# 2_FPGA.net
KiCad netlist of a schematic drawn in Altium Designer
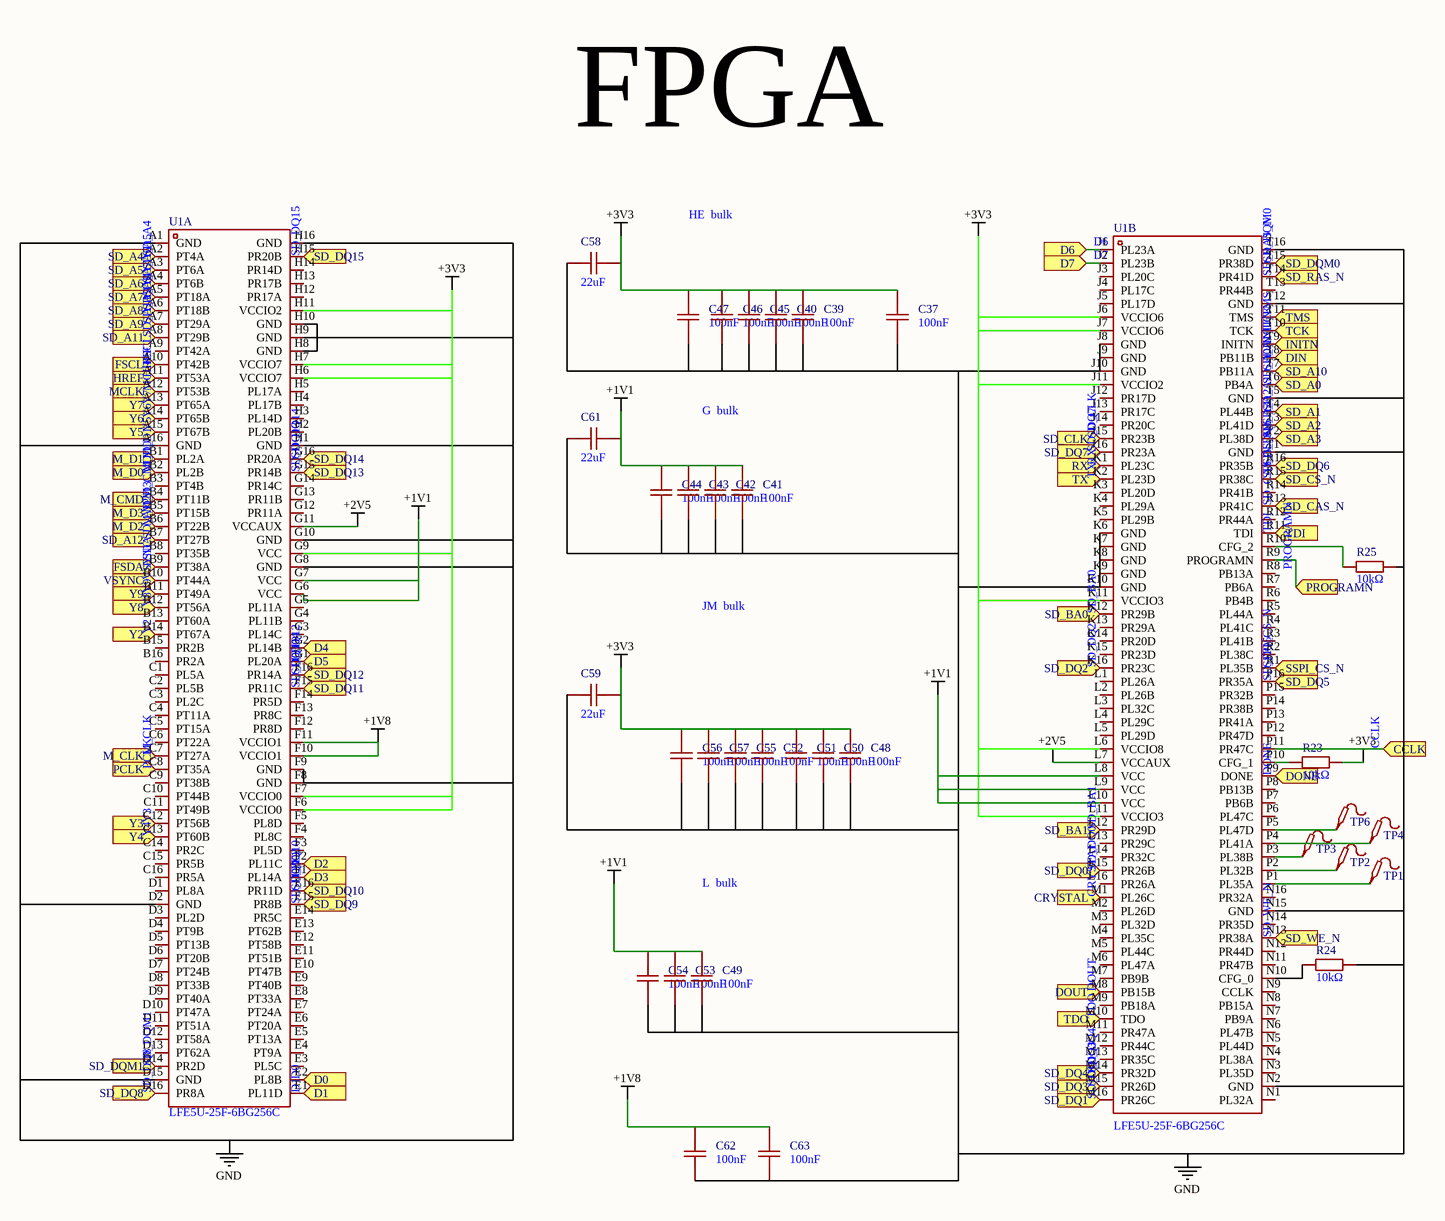
[diagram p0: 2_FPGA.schdoc]

(export (version "E")
  (design (tool "Eeschema 10.0.6"))
  (components
    (comp (ref "C37")
      (value "100nF")
      (footprint "C01005")
      (fields
        (field (name "MANUFACTURER") "muRata(村田)")
        (field (name "MANUFACTURER PART") "GRM022R60J104KE15D")
        (field (name "TOLERANCE") "±10%")
      )
      (libsource (lib "altium-import") (part "root_2_GRM022R60J104KE15D_"))
    )
    (comp (ref "C39")
      (value "100nF")
      (footprint "C01005")
      (fields
        (field (name "MANUFACTURER") "muRata(村田)")
        (field (name "MANUFACTURER PART") "GRM022R60J104KE15D")
        (field (name "TOLERANCE") "±10%")
      )
      (libsource (lib "altium-import") (part "root_2_GRM022R60J104KE15D_"))
    )
    (comp (ref "C40")
      (value "100nF")
      (footprint "C01005")
      (fields
        (field (name "MANUFACTURER") "muRata(村田)")
        (field (name "MANUFACTURER PART") "GRM022R60J104KE15D")
        (field (name "TOLERANCE") "±10%")
      )
      (libsource (lib "altium-import") (part "root_2_GRM022R60J104KE15D_"))
    )
    (comp (ref "C41")
      (value "100nF")
      (footprint "C01005")
      (fields
        (field (name "MANUFACTURER") "muRata(村田)")
        (field (name "MANUFACTURER PART") "GRM022R60J104KE15D")
        (field (name "TOLERANCE") "±10%")
      )
      (libsource (lib "altium-import") (part "root_2_GRM022R60J104KE15D_"))
    )
    (comp (ref "C42")
      (value "100nF")
      (footprint "C01005")
      (fields
        (field (name "MANUFACTURER") "muRata(村田)")
        (field (name "MANUFACTURER PART") "GRM022R60J104KE15D")
        (field (name "TOLERANCE") "±10%")
      )
      (libsource (lib "altium-import") (part "root_2_GRM022R60J104KE15D_"))
    )
    (comp (ref "C43")
      (value "100nF")
      (footprint "C01005")
      (fields
        (field (name "MANUFACTURER") "muRata(村田)")
        (field (name "MANUFACTURER PART") "GRM022R60J104KE15D")
        (field (name "TOLERANCE") "±10%")
      )
      (libsource (lib "altium-import") (part "root_2_GRM022R60J104KE15D_"))
    )
    (comp (ref "C44")
      (value "100nF")
      (footprint "C01005")
      (fields
        (field (name "MANUFACTURER") "muRata(村田)")
        (field (name "MANUFACTURER PART") "GRM022R60J104KE15D")
        (field (name "TOLERANCE") "±10%")
      )
      (libsource (lib "altium-import") (part "root_2_GRM022R60J104KE15D_"))
    )
    (comp (ref "C45")
      (value "100nF")
      (footprint "C01005")
      (fields
        (field (name "MANUFACTURER") "muRata(村田)")
        (field (name "MANUFACTURER PART") "GRM022R60J104KE15D")
        (field (name "TOLERANCE") "±10%")
      )
      (libsource (lib "altium-import") (part "root_2_GRM022R60J104KE15D_"))
    )
    (comp (ref "C46")
      (value "100nF")
      (footprint "C01005")
      (fields
        (field (name "MANUFACTURER") "muRata(村田)")
        (field (name "MANUFACTURER PART") "GRM022R60J104KE15D")
        (field (name "TOLERANCE") "±10%")
      )
      (libsource (lib "altium-import") (part "root_2_GRM022R60J104KE15D_"))
    )
    (comp (ref "C47")
      (value "100nF")
      (footprint "C01005")
      (fields
        (field (name "MANUFACTURER") "muRata(村田)")
        (field (name "MANUFACTURER PART") "GRM022R60J104KE15D")
        (field (name "TOLERANCE") "±10%")
      )
      (libsource (lib "altium-import") (part "root_2_GRM022R60J104KE15D_"))
    )
    (comp (ref "C48")
      (value "100nF")
      (footprint "C01005")
      (fields
        (field (name "MANUFACTURER") "muRata(村田)")
        (field (name "MANUFACTURER PART") "GRM022R60J104KE15D")
        (field (name "TOLERANCE") "±10%")
      )
      (libsource (lib "altium-import") (part "root_2_GRM022R60J104KE15D_"))
    )
    (comp (ref "C49")
      (value "100nF")
      (footprint "C01005")
      (fields
        (field (name "MANUFACTURER") "muRata(村田)")
        (field (name "MANUFACTURER PART") "GRM022R60J104KE15D")
        (field (name "TOLERANCE") "±10%")
      )
      (libsource (lib "altium-import") (part "root_2_GRM022R60J104KE15D_"))
    )
    (comp (ref "C50")
      (value "100nF")
      (footprint "C01005")
      (fields
        (field (name "MANUFACTURER") "muRata(村田)")
        (field (name "MANUFACTURER PART") "GRM022R60J104KE15D")
        (field (name "TOLERANCE") "±10%")
      )
      (libsource (lib "altium-import") (part "root_2_GRM022R60J104KE15D_"))
    )
    (comp (ref "C51")
      (value "100nF")
      (footprint "C01005")
      (fields
        (field (name "MANUFACTURER") "muRata(村田)")
        (field (name "MANUFACTURER PART") "GRM022R60J104KE15D")
        (field (name "TOLERANCE") "±10%")
      )
      (libsource (lib "altium-import") (part "root_2_GRM022R60J104KE15D_"))
    )
    (comp (ref "C52")
      (value "100nF")
      (footprint "C01005")
      (fields
        (field (name "MANUFACTURER") "muRata(村田)")
        (field (name "MANUFACTURER PART") "GRM022R60J104KE15D")
        (field (name "TOLERANCE") "±10%")
      )
      (libsource (lib "altium-import") (part "root_2_GRM022R60J104KE15D_"))
    )
    (comp (ref "C53")
      (value "100nF")
      (footprint "C01005")
      (fields
        (field (name "MANUFACTURER") "muRata(村田)")
        (field (name "MANUFACTURER PART") "GRM022R60J104KE15D")
        (field (name "TOLERANCE") "±10%")
      )
      (libsource (lib "altium-import") (part "root_2_GRM022R60J104KE15D_"))
    )
    (comp (ref "C54")
      (value "100nF")
      (footprint "C01005")
      (fields
        (field (name "MANUFACTURER") "muRata(村田)")
        (field (name "MANUFACTURER PART") "GRM022R60J104KE15D")
        (field (name "TOLERANCE") "±10%")
      )
      (libsource (lib "altium-import") (part "root_2_GRM022R60J104KE15D_"))
    )
    (comp (ref "C55")
      (value "100nF")
      (footprint "C01005")
      (fields
        (field (name "MANUFACTURER") "muRata(村田)")
        (field (name "MANUFACTURER PART") "GRM022R60J104KE15D")
        (field (name "TOLERANCE") "±10%")
      )
      (libsource (lib "altium-import") (part "root_2_GRM022R60J104KE15D_"))
    )
    (comp (ref "C56")
      (value "100nF")
      (footprint "C01005")
      (fields
        (field (name "MANUFACTURER") "muRata(村田)")
        (field (name "MANUFACTURER PART") "GRM022R60J104KE15D")
        (field (name "TOLERANCE") "±10%")
      )
      (libsource (lib "altium-import") (part "root_2_GRM022R60J104KE15D_"))
    )
    (comp (ref "C57")
      (value "100nF")
      (footprint "C01005")
      (fields
        (field (name "MANUFACTURER") "muRata(村田)")
        (field (name "MANUFACTURER PART") "GRM022R60J104KE15D")
        (field (name "TOLERANCE") "±10%")
      )
      (libsource (lib "altium-import") (part "root_2_GRM022R60J104KE15D_"))
    )
    (comp (ref "C58")
      (value "22uF")
      (footprint "C0603")
      (fields
        (field (name "MANUFACTURER") "CCTC(三环)")
        (field (name "MANUFACTURER PART") "TCC0603X5R226M6R3CT")
        (field (name "TOLERANCE") "±20%")
      )
      (libsource (lib "altium-import") (part "root_1_TCC0603X5R226M6R3CT_"))
    )
    (comp (ref "C59")
      (value "22uF")
      (footprint "C0603")
      (fields
        (field (name "MANUFACTURER") "CCTC(三环)")
        (field (name "MANUFACTURER PART") "TCC0603X5R226M6R3CT")
        (field (name "TOLERANCE") "±20%")
      )
      (libsource (lib "altium-import") (part "root_1_TCC0603X5R226M6R3CT_"))
    )
    (comp (ref "C61")
      (value "22uF")
      (footprint "C0603")
      (fields
        (field (name "MANUFACTURER") "CCTC(三环)")
        (field (name "MANUFACTURER PART") "TCC0603X5R226M6R3CT")
        (field (name "TOLERANCE") "±20%")
      )
      (libsource (lib "altium-import") (part "root_1_TCC0603X5R226M6R3CT_"))
    )
    (comp (ref "C62")
      (value "100nF")
      (footprint "C01005")
      (fields
        (field (name "MANUFACTURER") "muRata(村田)")
        (field (name "MANUFACTURER PART") "GRM022R60J104KE15D")
        (field (name "TOLERANCE") "±10%")
      )
      (libsource (lib "altium-import") (part "root_2_GRM022R60J104KE15D_"))
    )
    (comp (ref "C63")
      (value "100nF")
      (footprint "C01005")
      (fields
        (field (name "MANUFACTURER") "muRata(村田)")
        (field (name "MANUFACTURER PART") "GRM022R60J104KE15D")
        (field (name "TOLERANCE") "±10%")
      )
      (libsource (lib "altium-import") (part "root_2_GRM022R60J104KE15D_"))
    )
    (comp (ref "R23")
      (value "10kΩ")
      (footprint "R0402")
      (fields
        (field (name "MANUFACTURER") "UNI-ROYAL(厚声)")
        (field (name "MANUFACTURER PART") "0402WGF1002TCE")
        (field (name "TOLERANCE") "±1%")
      )
      (libsource (lib "altium-import") (part "root_2_0402WGF1002TCE_"))
    )
    (comp (ref "R24")
      (value "10kΩ")
      (footprint "R0402")
      (fields
        (field (name "MANUFACTURER") "UNI-ROYAL(厚声)")
        (field (name "MANUFACTURER PART") "0402WGF1002TCE")
        (field (name "TOLERANCE") "±1%")
      )
      (libsource (lib "altium-import") (part "root_2_0402WGF1002TCE_"))
    )
    (comp (ref "R25")
      (value "10kΩ")
      (footprint "R0402")
      (fields
        (field (name "MANUFACTURER") "UNI-ROYAL(厚声)")
        (field (name "MANUFACTURER PART") "0402WGF1002TCE")
        (field (name "TOLERANCE") "±1%")
      )
      (libsource (lib "altium-import") (part "root_2_0402WGF1002TCE_"))
    )
    (comp (ref "TP1")
      (value "~")
      (footprint "Test-Point-0.5mm")
      (libsource (lib "altium-import") (part "root_0_Test-Point_"))
    )
    (comp (ref "TP2")
      (value "~")
      (footprint "Test-Point-0.5mm")
      (libsource (lib "altium-import") (part "root_0_Test-Point_"))
    )
    (comp (ref "TP3")
      (value "~")
      (footprint "Test-Point-0.5mm")
      (libsource (lib "altium-import") (part "root_0_Test-Point_"))
    )
    (comp (ref "TP4")
      (value "~")
      (footprint "Test-Point-0.5mm")
      (libsource (lib "altium-import") (part "root_0_Test-Point_"))
    )
    (comp (ref "TP6")
      (value "~")
      (footprint "Test-Point-0.5mm")
      (libsource (lib "altium-import") (part "root_0_Test-Point_"))
    )
    (comp (ref "U1")
      (value "LFE5U-25F-6BG256C")
      (footprint "CABGA-256_L14.0-W14.0-R16-C16-P0.80-TL")
      (fields (field (name "MANUFACTURER") "LATTICE(莱迪思)"))
      (libsource (lib "altium-import") (part "root_0_LFE5U-25F-6BG256C_"))
    )
  )
  (nets
    (net (code "1") (name "+1V1") (class "Default")
      (node (ref "C41") (pin "1") (pinfunction "1_1") (pintype "passive"))
      (node (ref "C42") (pin "1") (pinfunction "1_1") (pintype "passive"))
      (node (ref "C43") (pin "1") (pinfunction "1_1") (pintype "passive"))
      (node (ref "C44") (pin "1") (pinfunction "1_1") (pintype "passive"))
      (node (ref "C49") (pin "1") (pinfunction "1_1") (pintype "passive"))
      (node (ref "C53") (pin "1") (pinfunction "1_1") (pintype "passive"))
      (node (ref "C54") (pin "1") (pinfunction "1_1") (pintype "passive"))
      (node (ref "C61") (pin "1") (pinfunction "1_1") (pintype "passive"))
      (node (ref "U1") (pin "G6") (pinfunction "VCC_G6") (pintype "passive"))
      (node (ref "U1") (pin "G7") (pinfunction "VCC_G7") (pintype "passive"))
      (node (ref "U1") (pin "L10") (pinfunction "VCC_L10") (pintype "passive"))
      (node (ref "U1") (pin "L8") (pinfunction "VCC_L8") (pintype "passive"))
      (node (ref "U1") (pin "L9") (pinfunction "VCC_L9") (pintype "passive"))
    )
    (net (code "2") (name "+1V8") (class "Default")
      (node (ref "C62") (pin "1") (pinfunction "1_1") (pintype "passive"))
      (node (ref "C63") (pin "1") (pinfunction "1_1") (pintype "passive"))
      (node (ref "U1") (pin "F10") (pinfunction "VCCIO1_F10") (pintype "passive"))
      (node (ref "U1") (pin "F11") (pinfunction "VCCIO1_F11") (pintype "passive"))
    )
    (net (code "3") (name "+2V5") (class "Default")
      (node (ref "U1") (pin "G11") (pinfunction "VCCAUX_G11") (pintype "passive"))
      (node (ref "U1") (pin "L7") (pinfunction "VCCAUX_L7") (pintype "passive"))
    )
    (net (code "4") (name "+3V3") (class "Default")
      (node (ref "C37") (pin "1") (pinfunction "1_1") (pintype "passive"))
      (node (ref "C39") (pin "1") (pinfunction "1_1") (pintype "passive"))
      (node (ref "C40") (pin "1") (pinfunction "1_1") (pintype "passive"))
      (node (ref "C45") (pin "1") (pinfunction "1_1") (pintype "passive"))
      (node (ref "C46") (pin "1") (pinfunction "1_1") (pintype "passive"))
      (node (ref "C47") (pin "1") (pinfunction "1_1") (pintype "passive"))
      (node (ref "C48") (pin "1") (pinfunction "1_1") (pintype "passive"))
      (node (ref "C50") (pin "1") (pinfunction "1_1") (pintype "passive"))
      (node (ref "C51") (pin "1") (pinfunction "1_1") (pintype "passive"))
      (node (ref "C52") (pin "1") (pinfunction "1_1") (pintype "passive"))
      (node (ref "C55") (pin "1") (pinfunction "1_1") (pintype "passive"))
      (node (ref "C56") (pin "1") (pinfunction "1_1") (pintype "passive"))
      (node (ref "C57") (pin "1") (pinfunction "1_1") (pintype "passive"))
      (node (ref "C58") (pin "1") (pinfunction "1_1") (pintype "passive"))
      (node (ref "C59") (pin "1") (pinfunction "1_1") (pintype "passive"))
      (node (ref "R23") (pin "1") (pinfunction "1_1") (pintype "passive"))
      (node (ref "U1") (pin "F6") (pinfunction "VCCIO0_F6") (pintype "passive"))
      (node (ref "U1") (pin "F7") (pinfunction "VCCIO0_F7") (pintype "passive"))
      (node (ref "U1") (pin "G9") (pinfunction "VCC_G9") (pintype "passive"))
      (node (ref "U1") (pin "H11") (pinfunction "VCCIO2_H11") (pintype "passive"))
      (node (ref "U1") (pin "H6") (pinfunction "VCCIO7_H6") (pintype "passive"))
      (node (ref "U1") (pin "H7") (pinfunction "VCCIO7_H7") (pintype "passive"))
      (node (ref "U1") (pin "J11") (pinfunction "VCCIO2_J11") (pintype "passive"))
      (node (ref "U1") (pin "J6") (pinfunction "VCCIO6_J6") (pintype "passive"))
      (node (ref "U1") (pin "J7") (pinfunction "VCCIO6_J7") (pintype "passive"))
      (node (ref "U1") (pin "K11") (pinfunction "VCCIO3_K11") (pintype "passive"))
      (node (ref "U1") (pin "L11") (pinfunction "VCCIO3_L11") (pintype "passive"))
      (node (ref "U1") (pin "L6") (pinfunction "VCCIO8_L6") (pintype "passive"))
    )
    (net (code "5") (name "/CCLK") (class "Default")
      (node (ref "U1") (pin "P11") (pinfunction "PR47C_P11") (pintype "passive"))
    )
    (net (code "6") (name "/CRYSTAL") (class "Default")
      (node (ref "U1") (pin "M1") (pinfunction "PL26C_M1") (pintype "passive"))
    )
    (net (code "7") (name "/D0") (class "Default")
      (node (ref "U1") (pin "E2") (pinfunction "PL8B_E2") (pintype "passive"))
    )
    (net (code "8") (name "/D1") (class "Default")
      (node (ref "U1") (pin "E1") (pinfunction "PL11D_E1") (pintype "passive"))
    )
    (net (code "9") (name "/D2") (class "Default")
      (node (ref "U1") (pin "F2") (pinfunction "PL11C_F2") (pintype "passive"))
    )
    (net (code "10") (name "/D3") (class "Default")
      (node (ref "U1") (pin "F1") (pinfunction "PL14A_F1") (pintype "passive"))
    )
    (net (code "11") (name "/D4") (class "Default")
      (node (ref "U1") (pin "G2") (pinfunction "PL14B_G2") (pintype "passive"))
    )
    (net (code "12") (name "/D5") (class "Default")
      (node (ref "U1") (pin "G1") (pinfunction "PL20A_G1") (pintype "passive"))
    )
    (net (code "13") (name "/D6") (class "Default")
      (node (ref "U1") (pin "J1") (pinfunction "PL23A_J1") (pintype "passive"))
    )
    (net (code "14") (name "/D7") (class "Default")
      (node (ref "U1") (pin "J2") (pinfunction "PL23B_J2") (pintype "passive"))
    )
    (net (code "15") (name "/DIN") (class "Default")
      (node (ref "U1") (pin "T8") (pinfunction "PB11B_T8") (pintype "passive"))
    )
    (net (code "16") (name "/DONE") (class "Default")
      (node (ref "U1") (pin "P9") (pinfunction "DONE_P9") (pintype "passive"))
    )
    (net (code "17") (name "/DOUT") (class "Default")
      (node (ref "U1") (pin "M8") (pinfunction "PB15B_M8") (pintype "passive"))
    )
    (net (code "18") (name "/FSCL") (class "Default")
      (node (ref "U1") (pin "A10") (pinfunction "PT42B_A10") (pintype "passive"))
    )
    (net (code "19") (name "/FSDA") (class "Default")
      (node (ref "U1") (pin "B9") (pinfunction "PT38A_B9") (pintype "passive"))
    )
    (net (code "20") (name "/HREF") (class "Default")
      (node (ref "U1") (pin "A11") (pinfunction "PT53A_A11") (pintype "passive"))
    )
    (net (code "21") (name "/INITN") (class "Default")
      (node (ref "U1") (pin "T9") (pinfunction "INITN_T9") (pintype "passive"))
    )
    (net (code "22") (name "/MCLK") (class "Default")
      (node (ref "U1") (pin "A12") (pinfunction "PT53B_A12") (pintype "passive"))
    )
    (net (code "23") (name "/M_CLK") (class "Default")
      (node (ref "U1") (pin "C7") (pinfunction "PT27A_C7") (pintype "passive"))
    )
    (net (code "24") (name "/M_CMD") (class "Default")
      (node (ref "U1") (pin "B4") (pinfunction "PT11B_B4") (pintype "passive"))
    )
    (net (code "25") (name "/M_D0") (class "Default")
      (node (ref "U1") (pin "B2") (pinfunction "PL2B_B2") (pintype "passive"))
    )
    (net (code "26") (name "/M_D1") (class "Default")
      (node (ref "U1") (pin "B1") (pinfunction "PL2A_B1") (pintype "passive"))
    )
    (net (code "27") (name "/M_D2") (class "Default")
      (node (ref "U1") (pin "B6") (pinfunction "PT22B_B6") (pintype "passive"))
    )
    (net (code "28") (name "/M_D3") (class "Default")
      (node (ref "U1") (pin "B5") (pinfunction "PT15B_B5") (pintype "passive"))
    )
    (net (code "29") (name "/PCLK") (class "Default")
      (node (ref "U1") (pin "C8") (pinfunction "PT35A_C8") (pintype "passive"))
    )
    (net (code "30") (name "/PROGRAMN") (class "Default")
      (node (ref "U1") (pin "R9") (pinfunction "PROGRAMN_R9") (pintype "passive"))
    )
    (net (code "31") (name "/RX") (class "Default")
      (node (ref "U1") (pin "K1") (pinfunction "PL23C_K1") (pintype "passive"))
    )
    (net (code "32") (name "/SD_A0") (class "Default")
      (node (ref "U1") (pin "T6") (pinfunction "PB4A_T6") (pintype "passive"))
    )
    (net (code "33") (name "/SD_A1") (class "Default")
      (node (ref "U1") (pin "T4") (pinfunction "PL44B_T4") (pintype "passive"))
    )
    (net (code "34") (name "/SD_A2") (class "Default")
      (node (ref "U1") (pin "T3") (pinfunction "PL41D_T3") (pintype "passive"))
    )
    (net (code "35") (name "/SD_A3") (class "Default")
      (node (ref "U1") (pin "T2") (pinfunction "PL38D_T2") (pintype "passive"))
    )
    (net (code "36") (name "/SD_A4") (class "Default")
      (node (ref "U1") (pin "A2") (pinfunction "PT4A_A2") (pintype "passive"))
    )
    (net (code "37") (name "/SD_A5") (class "Default")
      (node (ref "U1") (pin "A3") (pinfunction "PT6A_A3") (pintype "passive"))
    )
    (net (code "38") (name "/SD_A6") (class "Default")
      (node (ref "U1") (pin "A4") (pinfunction "PT6B_A4") (pintype "passive"))
    )
    (net (code "39") (name "/SD_A7") (class "Default")
      (node (ref "U1") (pin "A5") (pinfunction "PT18A_A5") (pintype "passive"))
    )
    (net (code "40") (name "/SD_A8") (class "Default")
      (node (ref "U1") (pin "A6") (pinfunction "PT18B_A6") (pintype "passive"))
    )
    (net (code "41") (name "/SD_A9") (class "Default")
      (node (ref "U1") (pin "A7") (pinfunction "PT29A_A7") (pintype "passive"))
    )
    (net (code "42") (name "/SD_A10") (class "Default")
      (node (ref "U1") (pin "T7") (pinfunction "PB11A_T7") (pintype "passive"))
    )
    (net (code "43") (name "/SD_A11") (class "Default")
      (node (ref "U1") (pin "A8") (pinfunction "PT29B_A8") (pintype "passive"))
    )
    (net (code "44") (name "/SD_A12") (class "Default")
      (node (ref "U1") (pin "B7") (pinfunction "PT27B_B7") (pintype "passive"))
    )
    (net (code "45") (name "/SD_BA0") (class "Default")
      (node (ref "U1") (pin "K12") (pinfunction "PR29B_K12") (pintype "passive"))
    )
    (net (code "46") (name "/SD_BA1") (class "Default")
      (node (ref "U1") (pin "L12") (pinfunction "PR29D_L12") (pintype "passive"))
    )
    (net (code "47") (name "/SD_CAS_N") (class "Default")
      (node (ref "U1") (pin "R13") (pinfunction "PR41C_R13") (pintype "passive"))
    )
    (net (code "48") (name "/SD_CLK") (class "Default")
      (node (ref "U1") (pin "J15") (pinfunction "PR23B_J15") (pintype "passive"))
    )
    (net (code "49") (name "/SD_CS_N") (class "Default")
      (node (ref "U1") (pin "R15") (pinfunction "PR38C_R15") (pintype "passive"))
    )
    (net (code "50") (name "/SD_DQ0") (class "Default")
      (node (ref "U1") (pin "L15") (pinfunction "PR26B_L15") (pintype "passive"))
    )
    (net (code "51") (name "/SD_DQ1") (class "Default")
      (node (ref "U1") (pin "M16") (pinfunction "PR26C_M16") (pintype "passive"))
    )
    (net (code "52") (name "/SD_DQ2") (class "Default")
      (node (ref "U1") (pin "K16") (pinfunction "PR23C_K16") (pintype "passive"))
    )
    (net (code "53") (name "/SD_DQ3") (class "Default")
      (node (ref "U1") (pin "M15") (pinfunction "PR26D_M15") (pintype "passive"))
    )
    (net (code "54") (name "/SD_DQ4") (class "Default")
      (node (ref "U1") (pin "M14") (pinfunction "PR32D_M14") (pintype "passive"))
    )
    (net (code "55") (name "/SD_DQ5") (class "Default")
      (node (ref "U1") (pin "P16") (pinfunction "PR35A_P16") (pintype "passive"))
    )
    (net (code "56") (name "/SD_DQ6") (class "Default")
      (node (ref "U1") (pin "R16") (pinfunction "PR35B_R16") (pintype "passive"))
    )
    (net (code "57") (name "/SD_DQ7") (class "Default")
      (node (ref "U1") (pin "J16") (pinfunction "PR23A_J16") (pintype "passive"))
    )
    (net (code "58") (name "/SD_DQ8") (class "Default")
      (node (ref "U1") (pin "D16") (pinfunction "PR8A_D16") (pintype "passive"))
    )
    (net (code "59") (name "/SD_DQ9") (class "Default")
      (node (ref "U1") (pin "E15") (pinfunction "PR8B_E15") (pintype "passive"))
    )
    (net (code "60") (name "/SD_DQ10") (class "Default")
      (node (ref "U1") (pin "E16") (pinfunction "PR11D_E16") (pintype "passive"))
    )
    (net (code "61") (name "/SD_DQ11") (class "Default")
      (node (ref "U1") (pin "F15") (pinfunction "PR11C_F15") (pintype "passive"))
    )
    (net (code "62") (name "/SD_DQ12") (class "Default")
      (node (ref "U1") (pin "F16") (pinfunction "PR14A_F16") (pintype "passive"))
    )
    (net (code "63") (name "/SD_DQ13") (class "Default")
      (node (ref "U1") (pin "G15") (pinfunction "PR14B_G15") (pintype "passive"))
    )
    (net (code "64") (name "/SD_DQ14") (class "Default")
      (node (ref "U1") (pin "G16") (pinfunction "PR20A_G16") (pintype "passive"))
    )
    (net (code "65") (name "/SD_DQ15") (class "Default")
      (node (ref "U1") (pin "H15") (pinfunction "PR20B_H15") (pintype "passive"))
    )
    (net (code "66") (name "/SD_DQM0") (class "Default")
      (node (ref "U1") (pin "T15") (pinfunction "PR38D_T15") (pintype "passive"))
    )
    (net (code "67") (name "/SD_DQM1") (class "Default")
      (node (ref "U1") (pin "D14") (pinfunction "PR2D_D14") (pintype "passive"))
    )
    (net (code "68") (name "/SD_RAS_N") (class "Default")
      (node (ref "U1") (pin "T14") (pinfunction "PR41D_T14") (pintype "passive"))
    )
    (net (code "69") (name "/SD_WE_N") (class "Default")
      (node (ref "U1") (pin "N13") (pinfunction "PR38A_N13") (pintype "passive"))
    )
    (net (code "70") (name "/SSPI_CS_N") (class "Default")
      (node (ref "U1") (pin "R1") (pinfunction "PL35B_R1") (pintype "passive"))
    )
    (net (code "71") (name "/TCK") (class "Default")
      (node (ref "U1") (pin "T10") (pinfunction "TCK_T10") (pintype "passive"))
    )
    (net (code "72") (name "/TDI") (class "Default")
      (node (ref "U1") (pin "R11") (pinfunction "TDI_R11") (pintype "passive"))
    )
    (net (code "73") (name "/TDO") (class "Default")
      (node (ref "U1") (pin "M10") (pinfunction "TDO_M10") (pintype "passive"))
    )
    (net (code "74") (name "/TMS") (class "Default")
      (node (ref "U1") (pin "T11") (pinfunction "TMS_T11") (pintype "passive"))
    )
    (net (code "75") (name "/TX") (class "Default")
      (node (ref "U1") (pin "K2") (pinfunction "PL23D_K2") (pintype "passive"))
    )
    (net (code "76") (name "/VSYNC") (class "Default")
      (node (ref "U1") (pin "B10") (pinfunction "PT44A_B10") (pintype "passive"))
    )
    (net (code "77") (name "/Y2") (class "Default")
      (node (ref "U1") (pin "B14") (pinfunction "PT67A_B14") (pintype "passive"))
    )
    (net (code "78") (name "/Y3") (class "Default")
      (node (ref "U1") (pin "C12") (pinfunction "PT56B_C12") (pintype "passive"))
    )
    (net (code "79") (name "/Y4") (class "Default")
      (node (ref "U1") (pin "C13") (pinfunction "PT60B_C13") (pintype "passive"))
    )
    (net (code "80") (name "/Y5") (class "Default")
      (node (ref "U1") (pin "A15") (pinfunction "PT67B_A15") (pintype "passive"))
    )
    (net (code "81") (name "/Y6") (class "Default")
      (node (ref "U1") (pin "A14") (pinfunction "PT65B_A14") (pintype "passive"))
    )
    (net (code "82") (name "/Y7") (class "Default")
      (node (ref "U1") (pin "A13") (pinfunction "PT65A_A13") (pintype "passive"))
    )
    (net (code "83") (name "/Y8") (class "Default")
      (node (ref "U1") (pin "B12") (pinfunction "PT56A_B12") (pintype "passive"))
    )
    (net (code "84") (name "/Y9") (class "Default")
      (node (ref "U1") (pin "B11") (pinfunction "PT49A_B11") (pintype "passive"))
    )
    (net (code "85") (name "GND") (class "Default")
      (node (ref "C37") (pin "2") (pinfunction "2_2") (pintype "passive"))
      (node (ref "C39") (pin "2") (pinfunction "2_2") (pintype "passive"))
      (node (ref "C40") (pin "2") (pinfunction "2_2") (pintype "passive"))
      (node (ref "C41") (pin "2") (pinfunction "2_2") (pintype "passive"))
      (node (ref "C42") (pin "2") (pinfunction "2_2") (pintype "passive"))
      (node (ref "C43") (pin "2") (pinfunction "2_2") (pintype "passive"))
      (node (ref "C44") (pin "2") (pinfunction "2_2") (pintype "passive"))
      (node (ref "C45") (pin "2") (pinfunction "2_2") (pintype "passive"))
      (node (ref "C46") (pin "2") (pinfunction "2_2") (pintype "passive"))
      (node (ref "C47") (pin "2") (pinfunction "2_2") (pintype "passive"))
      (node (ref "C48") (pin "2") (pinfunction "2_2") (pintype "passive"))
      (node (ref "C49") (pin "2") (pinfunction "2_2") (pintype "passive"))
      (node (ref "C50") (pin "2") (pinfunction "2_2") (pintype "passive"))
      (node (ref "C51") (pin "2") (pinfunction "2_2") (pintype "passive"))
      (node (ref "C52") (pin "2") (pinfunction "2_2") (pintype "passive"))
      (node (ref "C53") (pin "2") (pinfunction "2_2") (pintype "passive"))
      (node (ref "C54") (pin "2") (pinfunction "2_2") (pintype "passive"))
      (node (ref "C55") (pin "2") (pinfunction "2_2") (pintype "passive"))
      (node (ref "C56") (pin "2") (pinfunction "2_2") (pintype "passive"))
      (node (ref "C57") (pin "2") (pinfunction "2_2") (pintype "passive"))
      (node (ref "C58") (pin "2") (pinfunction "2_2") (pintype "passive"))
      (node (ref "C59") (pin "2") (pinfunction "2_2") (pintype "passive"))
      (node (ref "C61") (pin "2") (pinfunction "2_2") (pintype "passive"))
      (node (ref "C62") (pin "2") (pinfunction "2_2") (pintype "passive"))
      (node (ref "C63") (pin "2") (pinfunction "2_2") (pintype "passive"))
      (node (ref "R24") (pin "1") (pinfunction "1_1") (pintype "passive"))
      (node (ref "R25") (pin "1") (pinfunction "1_1") (pintype "passive"))
      (node (ref "U1") (pin "A1") (pinfunction "GND_A1") (pintype "passive"))
      (node (ref "U1") (pin "A16") (pinfunction "GND_A16") (pintype "passive"))
      (node (ref "U1") (pin "D15") (pinfunction "GND_D15") (pintype "passive"))
      (node (ref "U1") (pin "D2") (pinfunction "GND_D2") (pintype "passive"))
      (node (ref "U1") (pin "F8") (pinfunction "GND_F8") (pintype "passive"))
      (node (ref "U1") (pin "F9") (pinfunction "GND_F9") (pintype "passive"))
      (node (ref "U1") (pin "G10") (pinfunction "GND_G10") (pintype "passive"))
      (node (ref "U1") (pin "G8") (pinfunction "GND_G8") (pintype "passive"))
      (node (ref "U1") (pin "H1") (pinfunction "GND_H1") (pintype "passive"))
      (node (ref "U1") (pin "H10") (pinfunction "GND_H10") (pintype "passive"))
      (node (ref "U1") (pin "H16") (pinfunction "GND_H16") (pintype "passive"))
      (node (ref "U1") (pin "H8") (pinfunction "GND_H8") (pintype "passive"))
      (node (ref "U1") (pin "H9") (pinfunction "GND_H9") (pintype "passive"))
      (node (ref "U1") (pin "J10") (pinfunction "GND_J10") (pintype "passive"))
      (node (ref "U1") (pin "J8") (pinfunction "GND_J8") (pintype "passive"))
      (node (ref "U1") (pin "J9") (pinfunction "GND_J9") (pintype "passive"))
      (node (ref "U1") (pin "K10") (pinfunction "GND_K10") (pintype "passive"))
      (node (ref "U1") (pin "K6") (pinfunction "GND_K6") (pintype "passive"))
      (node (ref "U1") (pin "K7") (pinfunction "GND_K7") (pintype "passive"))
      (node (ref "U1") (pin "K8") (pinfunction "GND_K8") (pintype "passive"))
      (node (ref "U1") (pin "K9") (pinfunction "GND_K9") (pintype "passive"))
      (node (ref "U1") (pin "N15") (pinfunction "GND_N15") (pintype "passive"))
      (node (ref "U1") (pin "N2") (pinfunction "GND_N2") (pintype "passive"))
      (node (ref "U1") (pin "T1") (pinfunction "GND_T1") (pintype "passive"))
      (node (ref "U1") (pin "T12") (pinfunction "GND_T12") (pintype "passive"))
      (node (ref "U1") (pin "T16") (pinfunction "GND_T16") (pintype "passive"))
      (node (ref "U1") (pin "T5") (pinfunction "GND_T5") (pintype "passive"))
    )
    (net (code "86") (name "Net-(U1B-CFG_0)") (class "Default")
      (node (ref "R24") (pin "2") (pinfunction "2_2") (pintype "passive"))
      (node (ref "U1") (pin "N10") (pinfunction "CFG_0_N10") (pintype "passive"))
    )
    (net (code "87") (name "Net-(U1B-CFG_1)") (class "Default")
      (node (ref "R23") (pin "2") (pinfunction "2_2") (pintype "passive"))
      (node (ref "U1") (pin "P10") (pinfunction "CFG_1_P10") (pintype "passive"))
    )
    (net (code "88") (name "Net-(U1B-CFG_2)") (class "Default")
      (node (ref "R25") (pin "2") (pinfunction "2_2") (pintype "passive"))
      (node (ref "U1") (pin "R10") (pinfunction "CFG_2_R10") (pintype "passive"))
    )
    (net (code "89") (name "Net-(U1B-PL32B)") (class "Default")
      (node (ref "TP2") (pin "1") (pinfunction "1_1") (pintype "passive"))
      (node (ref "U1") (pin "P2") (pinfunction "PL32B_P2") (pintype "passive"))
    )
    (net (code "90") (name "Net-(U1B-PL35A)") (class "Default")
      (node (ref "TP1") (pin "1") (pinfunction "1_1") (pintype "passive"))
      (node (ref "U1") (pin "P1") (pinfunction "PL35A_P1") (pintype "passive"))
    )
    (net (code "91") (name "Net-(U1B-PL38B)") (class "Default")
      (node (ref "TP3") (pin "1") (pinfunction "1_1") (pintype "passive"))
      (node (ref "U1") (pin "P3") (pinfunction "PL38B_P3") (pintype "passive"))
    )
    (net (code "92") (name "Net-(U1B-PL41A)") (class "Default")
      (node (ref "TP4") (pin "1") (pinfunction "1_1") (pintype "passive"))
      (node (ref "U1") (pin "P4") (pinfunction "PL41A_P4") (pintype "passive"))
    )
    (net (code "93") (name "Net-(U1B-PL47D)") (class "Default")
      (node (ref "TP6") (pin "1") (pinfunction "1_1") (pintype "passive"))
      (node (ref "U1") (pin "P5") (pinfunction "PL47D_P5") (pintype "passive"))
    )
    (net (code "94") (name "unconnected-(U1A-PL2C-PadC3)") (class "Default")
      (node (ref "U1") (pin "C3") (pinfunction "PL2C_C3") (pintype "passive"))
    )
    (net (code "95") (name "unconnected-(U1A-PL2D-PadD3)") (class "Default")
      (node (ref "U1") (pin "D3") (pinfunction "PL2D_D3") (pintype "passive"))
    )
    (net (code "96") (name "unconnected-(U1A-PL5A-PadC1)") (class "Default")
      (node (ref "U1") (pin "C1") (pinfunction "PL5A_C1") (pintype "passive"))
    )
    (net (code "97") (name "unconnected-(U1A-PL5B-PadC2)") (class "Default")
      (node (ref "U1") (pin "C2") (pinfunction "PL5B_C2") (pintype "passive"))
    )
    (net (code "98") (name "unconnected-(U1A-PL5C-PadE3)") (class "Default")
      (node (ref "U1") (pin "E3") (pinfunction "PL5C_E3") (pintype "passive"))
    )
    (net (code "99") (name "unconnected-(U1A-PL5D-PadF3)") (class "Default")
      (node (ref "U1") (pin "F3") (pinfunction "PL5D_F3") (pintype "passive"))
    )
    (net (code "100") (name "unconnected-(U1A-PL8A-PadD1)") (class "Default")
      (node (ref "U1") (pin "D1") (pinfunction "PL8A_D1") (pintype "passive"))
    )
    (net (code "101") (name "unconnected-(U1A-PL8C-PadF4)") (class "Default")
      (node (ref "U1") (pin "F4") (pinfunction "PL8C_F4") (pintype "passive"))
    )
    (net (code "102") (name "unconnected-(U1A-PL8D-PadF5)") (class "Default")
      (node (ref "U1") (pin "F5") (pinfunction "PL8D_F5") (pintype "passive"))
    )
    (net (code "103") (name "unconnected-(U1A-PL11A-PadG5)") (class "Default")
      (node (ref "U1") (pin "G5") (pinfunction "PL11A_G5") (pintype "passive"))
    )
    (net (code "104") (name "unconnected-(U1A-PL11B-PadG4)") (class "Default")
      (node (ref "U1") (pin "G4") (pinfunction "PL11B_G4") (pintype "passive"))
    )
    (net (code "105") (name "unconnected-(U1A-PL14C-PadG3)") (class "Default")
      (node (ref "U1") (pin "G3") (pinfunction "PL14C_G3") (pintype "passive"))
    )
    (net (code "106") (name "unconnected-(U1A-PL14D-PadH3)") (class "Default")
      (node (ref "U1") (pin "H3") (pinfunction "PL14D_H3") (pintype "passive"))
    )
    (net (code "107") (name "unconnected-(U1A-PL17A-PadH5)") (class "Default")
      (node (ref "U1") (pin "H5") (pinfunction "PL17A_H5") (pintype "passive"))
    )
    (net (code "108") (name "unconnected-(U1A-PL17B-PadH4)") (class "Default")
      (node (ref "U1") (pin "H4") (pinfunction "PL17B_H4") (pintype "passive"))
    )
    (net (code "109") (name "unconnected-(U1A-PL20B-PadH2)") (class "Default")
      (node (ref "U1") (pin "H2") (pinfunction "PL20B_H2") (pintype "passive"))
    )
    (net (code "110") (name "unconnected-(U1A-PR2A-PadB16)") (class "Default")
      (node (ref "U1") (pin "B16") (pinfunction "PR2A_B16") (pintype "passive"))
    )
    (net (code "111") (name "unconnected-(U1A-PR2B-PadB15)") (class "Default")
      (node (ref "U1") (pin "B15") (pinfunction "PR2B_B15") (pintype "passive"))
    )
    (net (code "112") (name "unconnected-(U1A-PR2C-PadC14)") (class "Default")
      (node (ref "U1") (pin "C14") (pinfunction "PR2C_C14") (pintype "passive"))
    )
    (net (code "113") (name "unconnected-(U1A-PR5A-PadC16)") (class "Default")
      (node (ref "U1") (pin "C16") (pinfunction "PR5A_C16") (pintype "passive"))
    )
    (net (code "114") (name "unconnected-(U1A-PR5B-PadC15)") (class "Default")
      (node (ref "U1") (pin "C15") (pinfunction "PR5B_C15") (pintype "passive"))
    )
    (net (code "115") (name "unconnected-(U1A-PR5C-PadE14)") (class "Default")
      (node (ref "U1") (pin "E14") (pinfunction "PR5C_E14") (pintype "passive"))
    )
    (net (code "116") (name "unconnected-(U1A-PR5D-PadF14)") (class "Default")
      (node (ref "U1") (pin "F14") (pinfunction "PR5D_F14") (pintype "passive"))
    )
    (net (code "117") (name "unconnected-(U1A-PR8C-PadF13)") (class "Default")
      (node (ref "U1") (pin "F13") (pinfunction "PR8C_F13") (pintype "passive"))
    )
    (net (code "118") (name "unconnected-(U1A-PR8D-PadF12)") (class "Default")
      (node (ref "U1") (pin "F12") (pinfunction "PR8D_F12") (pintype "passive"))
    )
    (net (code "119") (name "unconnected-(U1A-PR11A-PadG12)") (class "Default")
      (node (ref "U1") (pin "G12") (pinfunction "PR11A_G12") (pintype "passive"))
    )
    (net (code "120") (name "unconnected-(U1A-PR11B-PadG13)") (class "Default")
      (node (ref "U1") (pin "G13") (pinfunction "PR11B_G13") (pintype "passive"))
    )
    (net (code "121") (name "unconnected-(U1A-PR14C-PadG14)") (class "Default")
      (node (ref "U1") (pin "G14") (pinfunction "PR14C_G14") (pintype "passive"))
    )
    (net (code "122") (name "unconnected-(U1A-PR14D-PadH14)") (class "Default")
      (node (ref "U1") (pin "H14") (pinfunction "PR14D_H14") (pintype "passive"))
    )
    (net (code "123") (name "unconnected-(U1A-PR17A-PadH12)") (class "Default")
      (node (ref "U1") (pin "H12") (pinfunction "PR17A_H12") (pintype "passive"))
    )
    (net (code "124") (name "unconnected-(U1A-PR17B-PadH13)") (class "Default")
      (node (ref "U1") (pin "H13") (pinfunction "PR17B_H13") (pintype "passive"))
    )
    (net (code "125") (name "unconnected-(U1A-PT4B-PadB3)") (class "Default")
      (node (ref "U1") (pin "B3") (pinfunction "PT4B_B3") (pintype "passive"))
    )
    (net (code "126") (name "unconnected-(U1A-PT9A-PadE4)") (class "Default")
      (node (ref "U1") (pin "E4") (pinfunction "PT9A_E4") (pintype "passive"))
    )
    (net (code "127") (name "unconnected-(U1A-PT9B-PadD4)") (class "Default")
      (node (ref "U1") (pin "D4") (pinfunction "PT9B_D4") (pintype "passive"))
    )
    (net (code "128") (name "unconnected-(U1A-PT11A-PadC4)") (class "Default")
      (node (ref "U1") (pin "C4") (pinfunction "PT11A_C4") (pintype "passive"))
    )
    (net (code "129") (name "unconnected-(U1A-PT13A-PadE5)") (class "Default")
      (node (ref "U1") (pin "E5") (pinfunction "PT13A_E5") (pintype "passive"))
    )
    (net (code "130") (name "unconnected-(U1A-PT13B-PadD5)") (class "Default")
      (node (ref "U1") (pin "D5") (pinfunction "PT13B_D5") (pintype "passive"))
    )
    (net (code "131") (name "unconnected-(U1A-PT15A-PadC5)") (class "Default")
      (node (ref "U1") (pin "C5") (pinfunction "PT15A_C5") (pintype "passive"))
    )
    (net (code "132") (name "unconnected-(U1A-PT20A-PadE6)") (class "Default")
      (node (ref "U1") (pin "E6") (pinfunction "PT20A_E6") (pintype "passive"))
    )
    (net (code "133") (name "unconnected-(U1A-PT20B-PadD6)") (class "Default")
      (node (ref "U1") (pin "D6") (pinfunction "PT20B_D6") (pintype "passive"))
    )
    (net (code "134") (name "unconnected-(U1A-PT22A-PadC6)") (class "Default")
      (node (ref "U1") (pin "C6") (pinfunction "PT22A_C6") (pintype "passive"))
    )
    (net (code "135") (name "unconnected-(U1A-PT24A-PadE7)") (class "Default")
      (node (ref "U1") (pin "E7") (pinfunction "PT24A_E7") (pintype "passive"))
    )
    (net (code "136") (name "unconnected-(U1A-PT24B-PadD7)") (class "Default")
      (node (ref "U1") (pin "D7") (pinfunction "PT24B_D7") (pintype "passive"))
    )
    (net (code "137") (name "unconnected-(U1A-PT33A-PadE8)") (class "Default")
      (node (ref "U1") (pin "E8") (pinfunction "PT33A_E8") (pintype "passive"))
    )
    (net (code "138") (name "unconnected-(U1A-PT33B-PadD8)") (class "Default")
      (node (ref "U1") (pin "D8") (pinfunction "PT33B_D8") (pintype "passive"))
    )
    (net (code "139") (name "unconnected-(U1A-PT35B-PadB8)") (class "Default")
      (node (ref "U1") (pin "B8") (pinfunction "PT35B_B8") (pintype "passive"))
    )
    (net (code "140") (name "unconnected-(U1A-PT38B-PadC9)") (class "Default")
      (node (ref "U1") (pin "C9") (pinfunction "PT38B_C9") (pintype "passive"))
    )
    (net (code "141") (name "unconnected-(U1A-PT40A-PadD9)") (class "Default")
      (node (ref "U1") (pin "D9") (pinfunction "PT40A_D9") (pintype "passive"))
    )
    (net (code "142") (name "unconnected-(U1A-PT40B-PadE9)") (class "Default")
      (node (ref "U1") (pin "E9") (pinfunction "PT40B_E9") (pintype "passive"))
    )
    (net (code "143") (name "unconnected-(U1A-PT42A-PadA9)") (class "Default")
      (node (ref "U1") (pin "A9") (pinfunction "PT42A_A9") (pintype "passive"))
    )
    (net (code "144") (name "unconnected-(U1A-PT44B-PadC10)") (class "Default")
      (node (ref "U1") (pin "C10") (pinfunction "PT44B_C10") (pintype "passive"))
    )
    (net (code "145") (name "unconnected-(U1A-PT47A-PadD10)") (class "Default")
      (node (ref "U1") (pin "D10") (pinfunction "PT47A_D10") (pintype "passive"))
    )
    (net (code "146") (name "unconnected-(U1A-PT47B-PadE10)") (class "Default")
      (node (ref "U1") (pin "E10") (pinfunction "PT47B_E10") (pintype "passive"))
    )
    (net (code "147") (name "unconnected-(U1A-PT49B-PadC11)") (class "Default")
      (node (ref "U1") (pin "C11") (pinfunction "PT49B_C11") (pintype "passive"))
    )
    (net (code "148") (name "unconnected-(U1A-PT51A-PadD11)") (class "Default")
      (node (ref "U1") (pin "D11") (pinfunction "PT51A_D11") (pintype "passive"))
    )
    (net (code "149") (name "unconnected-(U1A-PT51B-PadE11)") (class "Default")
      (node (ref "U1") (pin "E11") (pinfunction "PT51B_E11") (pintype "passive"))
    )
    (net (code "150") (name "unconnected-(U1A-PT58A-PadD12)") (class "Default")
      (node (ref "U1") (pin "D12") (pinfunction "PT58A_D12") (pintype "passive"))
    )
    (net (code "151") (name "unconnected-(U1A-PT58B-PadE12)") (class "Default")
      (node (ref "U1") (pin "E12") (pinfunction "PT58B_E12") (pintype "passive"))
    )
    (net (code "152") (name "unconnected-(U1A-PT60A-PadB13)") (class "Default")
      (node (ref "U1") (pin "B13") (pinfunction "PT60A_B13") (pintype "passive"))
    )
    (net (code "153") (name "unconnected-(U1A-PT62A-PadD13)") (class "Default")
      (node (ref "U1") (pin "D13") (pinfunction "PT62A_D13") (pintype "passive"))
    )
    (net (code "154") (name "unconnected-(U1A-PT62B-PadE13)") (class "Default")
      (node (ref "U1") (pin "E13") (pinfunction "PT62B_E13") (pintype "passive"))
    )
    (net (code "155") (name "unconnected-(U1B-CCLK-PadN9)") (class "Default")
      (node (ref "U1") (pin "N9") (pinfunction "CCLK_N9") (pintype "passive"))
    )
    (net (code "156") (name "unconnected-(U1B-PB4B-PadR6)") (class "Default")
      (node (ref "U1") (pin "R6") (pinfunction "PB4B_R6") (pintype "passive"))
    )
    (net (code "157") (name "unconnected-(U1B-PB6A-PadR7)") (class "Default")
      (node (ref "U1") (pin "R7") (pinfunction "PB6A_R7") (pintype "passive"))
    )
    (net (code "158") (name "unconnected-(U1B-PB6B-PadP7)") (class "Default")
      (node (ref "U1") (pin "P7") (pinfunction "PB6B_P7") (pintype "passive"))
    )
    (net (code "159") (name "unconnected-(U1B-PB9A-PadN7)") (class "Default")
      (node (ref "U1") (pin "N7") (pinfunction "PB9A_N7") (pintype "passive"))
    )
    (net (code "160") (name "unconnected-(U1B-PB9B-PadM7)") (class "Default")
      (node (ref "U1") (pin "M7") (pinfunction "PB9B_M7") (pintype "passive"))
    )
    (net (code "161") (name "unconnected-(U1B-PB13A-PadR8)") (class "Default")
      (node (ref "U1") (pin "R8") (pinfunction "PB13A_R8") (pintype "passive"))
    )
    (net (code "162") (name "unconnected-(U1B-PB13B-PadP8)") (class "Default")
      (node (ref "U1") (pin "P8") (pinfunction "PB13B_P8") (pintype "passive"))
    )
    (net (code "163") (name "unconnected-(U1B-PB15A-PadN8)") (class "Default")
      (node (ref "U1") (pin "N8") (pinfunction "PB15A_N8") (pintype "passive"))
    )
    (net (code "164") (name "unconnected-(U1B-PB18A-PadM9)") (class "Default")
      (node (ref "U1") (pin "M9") (pinfunction "PB18A_M9") (pintype "passive"))
    )
    (net (code "165") (name "unconnected-(U1B-PL17C-PadJ4)") (class "Default")
      (node (ref "U1") (pin "J4") (pinfunction "PL17C_J4") (pintype "passive"))
    )
    (net (code "166") (name "unconnected-(U1B-PL17D-PadJ5)") (class "Default")
      (node (ref "U1") (pin "J5") (pinfunction "PL17D_J5") (pintype "passive"))
    )
    (net (code "167") (name "unconnected-(U1B-PL20C-PadJ3)") (class "Default")
      (node (ref "U1") (pin "J3") (pinfunction "PL20C_J3") (pintype "passive"))
    )
    (net (code "168") (name "unconnected-(U1B-PL20D-PadK3)") (class "Default")
      (node (ref "U1") (pin "K3") (pinfunction "PL20D_K3") (pintype "passive"))
    )
    (net (code "169") (name "unconnected-(U1B-PL26A-PadL1)") (class "Default")
      (node (ref "U1") (pin "L1") (pinfunction "PL26A_L1") (pintype "passive"))
    )
    (net (code "170") (name "unconnected-(U1B-PL26B-PadL2)") (class "Default")
      (node (ref "U1") (pin "L2") (pinfunction "PL26B_L2") (pintype "passive"))
    )
    (net (code "171") (name "unconnected-(U1B-PL26D-PadM2)") (class "Default")
      (node (ref "U1") (pin "M2") (pinfunction "PL26D_M2") (pintype "passive"))
    )
    (net (code "172") (name "unconnected-(U1B-PL29A-PadK4)") (class "Default")
      (node (ref "U1") (pin "K4") (pinfunction "PL29A_K4") (pintype "passive"))
    )
    (net (code "173") (name "unconnected-(U1B-PL29B-PadK5)") (class "Default")
      (node (ref "U1") (pin "K5") (pinfunction "PL29B_K5") (pintype "passive"))
    )
    (net (code "174") (name "unconnected-(U1B-PL29C-PadL4)") (class "Default")
      (node (ref "U1") (pin "L4") (pinfunction "PL29C_L4") (pintype "passive"))
    )
    (net (code "175") (name "unconnected-(U1B-PL29D-PadL5)") (class "Default")
      (node (ref "U1") (pin "L5") (pinfunction "PL29D_L5") (pintype "passive"))
    )
    (net (code "176") (name "unconnected-(U1B-PL32A-PadN1)") (class "Default")
      (node (ref "U1") (pin "N1") (pinfunction "PL32A_N1") (pintype "passive"))
    )
    (net (code "177") (name "unconnected-(U1B-PL32C-PadL3)") (class "Default")
      (node (ref "U1") (pin "L3") (pinfunction "PL32C_L3") (pintype "passive"))
    )
    (net (code "178") (name "unconnected-(U1B-PL32D-PadM3)") (class "Default")
      (node (ref "U1") (pin "M3") (pinfunction "PL32D_M3") (pintype "passive"))
    )
    (net (code "179") (name "unconnected-(U1B-PL35C-PadM4)") (class "Default")
      (node (ref "U1") (pin "M4") (pinfunction "PL35C_M4") (pintype "passive"))
    )
    (net (code "180") (name "unconnected-(U1B-PL35D-PadN3)") (class "Default")
      (node (ref "U1") (pin "N3") (pinfunction "PL35D_N3") (pintype "passive"))
    )
    (net (code "181") (name "unconnected-(U1B-PL38A-PadN4)") (class "Default")
      (node (ref "U1") (pin "N4") (pinfunction "PL38A_N4") (pintype "passive"))
    )
    (net (code "182") (name "unconnected-(U1B-PL38C-PadR2)") (class "Default")
      (node (ref "U1") (pin "R2") (pinfunction "PL38C_R2") (pintype "passive"))
    )
    (net (code "183") (name "unconnected-(U1B-PL41B-PadR3)") (class "Default")
      (node (ref "U1") (pin "R3") (pinfunction "PL41B_R3") (pintype "passive"))
    )
    (net (code "184") (name "unconnected-(U1B-PL41C-PadR4)") (class "Default")
      (node (ref "U1") (pin "R4") (pinfunction "PL41C_R4") (pintype "passive"))
    )
    (net (code "185") (name "unconnected-(U1B-PL44A-PadR5)") (class "Default")
      (node (ref "U1") (pin "R5") (pinfunction "PL44A_R5") (pintype "passive"))
    )
    (net (code "186") (name "unconnected-(U1B-PL44C-PadM5)") (class "Default")
      (node (ref "U1") (pin "M5") (pinfunction "PL44C_M5") (pintype "passive"))
    )
    (net (code "187") (name "unconnected-(U1B-PL44D-PadN5)") (class "Default")
      (node (ref "U1") (pin "N5") (pinfunction "PL44D_N5") (pintype "passive"))
    )
    (net (code "188") (name "unconnected-(U1B-PL47A-PadM6)") (class "Default")
      (node (ref "U1") (pin "M6") (pinfunction "PL47A_M6") (pintype "passive"))
    )
    (net (code "189") (name "unconnected-(U1B-PL47B-PadN6)") (class "Default")
      (node (ref "U1") (pin "N6") (pinfunction "PL47B_N6") (pintype "passive"))
    )
    (net (code "190") (name "unconnected-(U1B-PL47C-PadP6)") (class "Default")
      (node (ref "U1") (pin "P6") (pinfunction "PL47C_P6") (pintype "passive"))
    )
    (net (code "191") (name "unconnected-(U1B-PR17C-PadJ13)") (class "Default")
      (node (ref "U1") (pin "J13") (pinfunction "PR17C_J13") (pintype "passive"))
    )
    (net (code "192") (name "unconnected-(U1B-PR17D-PadJ12)") (class "Default")
      (node (ref "U1") (pin "J12") (pinfunction "PR17D_J12") (pintype "passive"))
    )
    (net (code "193") (name "unconnected-(U1B-PR20C-PadJ14)") (class "Default")
      (node (ref "U1") (pin "J14") (pinfunction "PR20C_J14") (pintype "passive"))
    )
    (net (code "194") (name "unconnected-(U1B-PR20D-PadK14)") (class "Default")
      (node (ref "U1") (pin "K14") (pinfunction "PR20D_K14") (pintype "passive"))
    )
    (net (code "195") (name "unconnected-(U1B-PR23D-PadK15)") (class "Default")
      (node (ref "U1") (pin "K15") (pinfunction "PR23D_K15") (pintype "passive"))
    )
    (net (code "196") (name "unconnected-(U1B-PR26A-PadL16)") (class "Default")
      (node (ref "U1") (pin "L16") (pinfunction "PR26A_L16") (pintype "passive"))
    )
    (net (code "197") (name "unconnected-(U1B-PR29A-PadK13)") (class "Default")
      (node (ref "U1") (pin "K13") (pinfunction "PR29A_K13") (pintype "passive"))
    )
    (net (code "198") (name "unconnected-(U1B-PR29C-PadL13)") (class "Default")
      (node (ref "U1") (pin "L13") (pinfunction "PR29C_L13") (pintype "passive"))
    )
    (net (code "199") (name "unconnected-(U1B-PR32A-PadN16)") (class "Default")
      (node (ref "U1") (pin "N16") (pinfunction "PR32A_N16") (pintype "passive"))
    )
    (net (code "200") (name "unconnected-(U1B-PR32B-PadP15)") (class "Default")
      (node (ref "U1") (pin "P15") (pinfunction "PR32B_P15") (pintype "passive"))
    )
    (net (code "201") (name "unconnected-(U1B-PR32C-PadL14)") (class "Default")
      (node (ref "U1") (pin "L14") (pinfunction "PR32C_L14") (pintype "passive"))
    )
    (net (code "202") (name "unconnected-(U1B-PR35C-PadM13)") (class "Default")
      (node (ref "U1") (pin "M13") (pinfunction "PR35C_M13") (pintype "passive"))
    )
    (net (code "203") (name "unconnected-(U1B-PR35D-PadN14)") (class "Default")
      (node (ref "U1") (pin "N14") (pinfunction "PR35D_N14") (pintype "passive"))
    )
    (net (code "204") (name "unconnected-(U1B-PR38B-PadP14)") (class "Default")
      (node (ref "U1") (pin "P14") (pinfunction "PR38B_P14") (pintype "passive"))
    )
    (net (code "205") (name "unconnected-(U1B-PR41A-PadP13)") (class "Default")
      (node (ref "U1") (pin "P13") (pinfunction "PR41A_P13") (pintype "passive"))
    )
    (net (code "206") (name "unconnected-(U1B-PR41B-PadR14)") (class "Default")
      (node (ref "U1") (pin "R14") (pinfunction "PR41B_R14") (pintype "passive"))
    )
    (net (code "207") (name "unconnected-(U1B-PR44A-PadR12)") (class "Default")
      (node (ref "U1") (pin "R12") (pinfunction "PR44A_R12") (pintype "passive"))
    )
    (net (code "208") (name "unconnected-(U1B-PR44B-PadT13)") (class "Default")
      (node (ref "U1") (pin "T13") (pinfunction "PR44B_T13") (pintype "passive"))
    )
    (net (code "209") (name "unconnected-(U1B-PR44C-PadM12)") (class "Default")
      (node (ref "U1") (pin "M12") (pinfunction "PR44C_M12") (pintype "passive"))
    )
    (net (code "210") (name "unconnected-(U1B-PR44D-PadN12)") (class "Default")
      (node (ref "U1") (pin "N12") (pinfunction "PR44D_N12") (pintype "passive"))
    )
    (net (code "211") (name "unconnected-(U1B-PR47A-PadM11)") (class "Default")
      (node (ref "U1") (pin "M11") (pinfunction "PR47A_M11") (pintype "passive"))
    )
    (net (code "212") (name "unconnected-(U1B-PR47B-PadN11)") (class "Default")
      (node (ref "U1") (pin "N11") (pinfunction "PR47B_N11") (pintype "passive"))
    )
    (net (code "213") (name "unconnected-(U1B-PR47D-PadP12)") (class "Default")
      (node (ref "U1") (pin "P12") (pinfunction "PR47D_P12") (pintype "passive"))
    )
  )
)
